# current-meter.net
KiCad netlist of a schematic drawn in Altium Designer
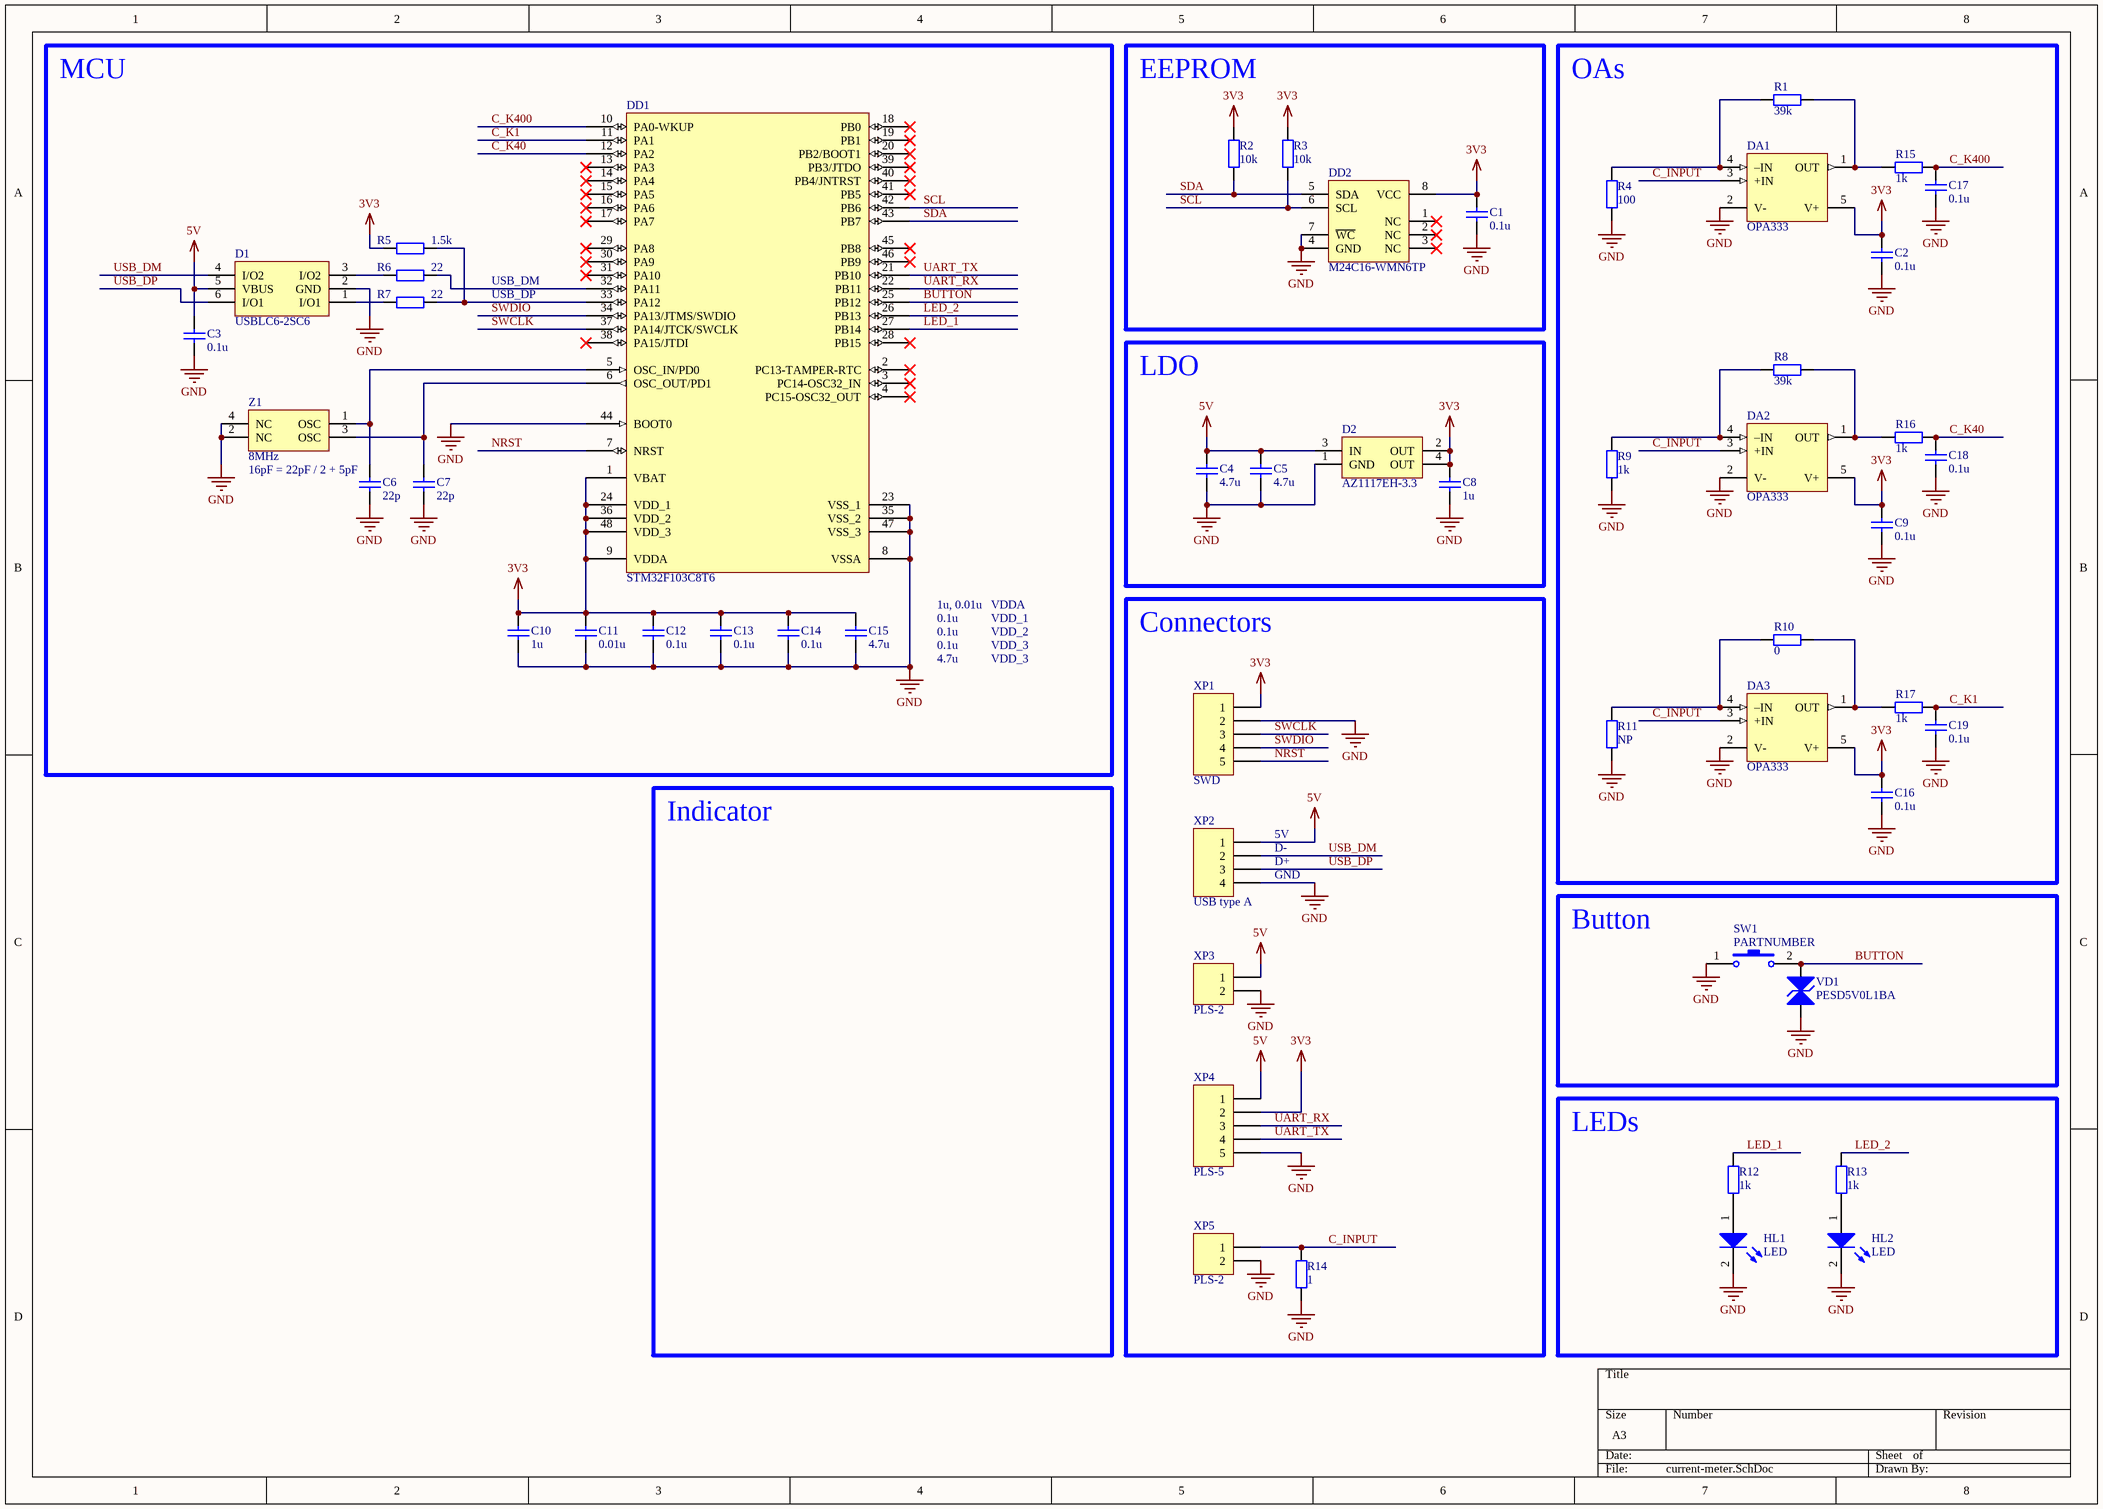
[diagram p0: current-meter.SchDoc]

(export (version "E")
  (design (tool "Eeschema 10.0.6"))
  (components
    (comp (ref "C1")
      (value "0.1u")
      (footprint "0603-CAP")
      (description "PARTNUMBER")
      (libsource (lib "Miscellaneous Devices") (part "Cap"))
    )
    (comp (ref "C2")
      (value "0.1u")
      (footprint "0603-CAP")
      (description "PARTNUMBER")
      (libsource (lib "Miscellaneous Devices") (part "Cap"))
    )
    (comp (ref "C3")
      (value "0.1u")
      (footprint "0603-CAP")
      (description "PARTNUMBER")
      (libsource (lib "Miscellaneous Devices") (part "Cap"))
    )
    (comp (ref "C4")
      (value "4.7u")
      (footprint "0805-CAP")
      (description "PARTNUMBER")
      (libsource (lib "Miscellaneous Devices") (part "Cap"))
    )
    (comp (ref "C5")
      (value "4.7u")
      (footprint "0805-CAP")
      (description "PARTNUMBER")
      (libsource (lib "Miscellaneous Devices") (part "Cap"))
    )
    (comp (ref "C6")
      (value "22p")
      (footprint "0603-CAP")
      (description "PARTNUMBER")
      (libsource (lib "Miscellaneous Devices") (part "Cap"))
    )
    (comp (ref "C7")
      (value "22p")
      (footprint "0603-CAP")
      (description "PARTNUMBER")
      (libsource (lib "Miscellaneous Devices") (part "Cap"))
    )
    (comp (ref "C8")
      (value "1u")
      (footprint "0805-CAP")
      (description "PARTNUMBER")
      (libsource (lib "Miscellaneous Devices") (part "Cap"))
    )
    (comp (ref "C9")
      (value "0.1u")
      (footprint "0603-CAP")
      (description "PARTNUMBER")
      (libsource (lib "Miscellaneous Devices") (part "Cap"))
    )
    (comp (ref "C10")
      (value "1u")
      (footprint "0805-CAP")
      (description "PARTNUMBER")
      (libsource (lib "Miscellaneous Devices") (part "Cap"))
    )
    (comp (ref "C11")
      (value "0.01u")
      (footprint "0603-CAP")
      (description "PARTNUMBER")
      (libsource (lib "Miscellaneous Devices") (part "Cap"))
    )
    (comp (ref "C12")
      (value "0.1u")
      (footprint "0603-CAP")
      (description "PARTNUMBER")
      (libsource (lib "Miscellaneous Devices") (part "Cap"))
    )
    (comp (ref "C13")
      (value "0.1u")
      (footprint "0603-CAP")
      (description "PARTNUMBER")
      (libsource (lib "Miscellaneous Devices") (part "Cap"))
    )
    (comp (ref "C14")
      (value "0.1u")
      (footprint "0603-CAP")
      (description "PARTNUMBER")
      (libsource (lib "Miscellaneous Devices") (part "Cap"))
    )
    (comp (ref "C15")
      (value "4.7u")
      (footprint "0805-CAP")
      (description "PARTNUMBER")
      (libsource (lib "Miscellaneous Devices") (part "Cap"))
    )
    (comp (ref "C16")
      (value "0.1u")
      (footprint "0603-CAP")
      (description "PARTNUMBER")
      (libsource (lib "Miscellaneous Devices") (part "Cap"))
    )
    (comp (ref "C17")
      (value "0.1u")
      (footprint "0603-CAP")
      (description "PARTNUMBER")
      (libsource (lib "Miscellaneous Devices") (part "Cap"))
    )
    (comp (ref "C18")
      (value "0.1u")
      (footprint "0603-CAP")
      (description "PARTNUMBER")
      (libsource (lib "Miscellaneous Devices") (part "Cap"))
    )
    (comp (ref "C19")
      (value "0.1u")
      (footprint "0603-CAP")
      (description "PARTNUMBER")
      (libsource (lib "Miscellaneous Devices") (part "Cap"))
    )
    (comp (ref "D1")
      (value "USBLC6-2SC6")
      (footprint "SOT-23-6L")
      (libsource (lib "sp-sharer-pcb") (part "USBLC6-2SC6"))
    )
    (comp (ref "D2")
      (value "AZ1117EH-3.3")
      (footprint "SOT-223")
      (description "AZ1117EH-3.3TRG1")
      (libsource (lib "sp-sharer-pcb") (part "AZ1117EH-3.3"))
    )
    (comp (ref "DA1")
      (value "OPA333")
      (footprint "SOT-23-5")
      (description "OPA333AIDBVR (TS321ILT)")
      (libsource (lib "current-meter") (part "OPA333"))
    )
    (comp (ref "DA2")
      (value "OPA333")
      (footprint "SOT-23-5")
      (description "OPA333AIDBVR (TS321ILT)")
      (libsource (lib "current-meter") (part "OPA333"))
    )
    (comp (ref "DA3")
      (value "OPA333")
      (footprint "SOT-23-5")
      (description "OPA333AIDBVR (TS321ILT)")
      (libsource (lib "current-meter") (part "OPA333"))
    )
    (comp (ref "DD1")
      (value "STM32F103C8T6")
      (footprint "LQFP48")
      (libsource (lib "sp-sharer-pcb") (part "STM32F103C8T6"))
    )
    (comp (ref "DD2")
      (value "M24C16-WMN6TP")
      (footprint "SOIC8")
      (libsource (lib "sp-sharer-pcb") (part "M24C16-WMN6TP"))
    )
    (comp (ref "HL1")
      (value "LED")
      (footprint "0603-LED")
      (description "PARTNUMBER")
      (libsource (lib "Miscellaneous Devices") (part "LED0"))
    )
    (comp (ref "HL2")
      (value "LED")
      (footprint "0603-LED")
      (description "PARTNUMBER")
      (libsource (lib "Miscellaneous Devices") (part "LED0"))
    )
    (comp (ref "R1")
      (value "39k")
      (footprint "0603-RES")
      (description "PARTNUMBER")
      (libsource (lib "") (part "Res2_3"))
    )
    (comp (ref "R2")
      (value "10k")
      (footprint "0603-RES")
      (description "PARTNUMBER")
      (libsource (lib "") (part "Res2_1"))
    )
    (comp (ref "R3")
      (value "10k")
      (footprint "0603-RES")
      (description "PARTNUMBER")
      (libsource (lib "") (part "Res2_1"))
    )
    (comp (ref "R4")
      (value "100")
      (footprint "0603-RES")
      (description "PARTNUMBER")
      (libsource (lib "Miscellaneous Devices") (part "Res2"))
    )
    (comp (ref "R5")
      (value "1.5k")
      (footprint "0603-RES")
      (description "PARTNUMBER")
      (libsource (lib "") (part "Res2_2"))
    )
    (comp (ref "R6")
      (value "22")
      (footprint "0603-RES")
      (description "PARTNUMBER")
      (libsource (lib "") (part "Res2_2"))
    )
    (comp (ref "R7")
      (value "22")
      (footprint "0603-RES")
      (description "PARTNUMBER")
      (libsource (lib "") (part "Res2_2"))
    )
    (comp (ref "R8")
      (value "39k")
      (footprint "0603-RES")
      (description "PARTNUMBER")
      (libsource (lib "") (part "Res2_3"))
    )
    (comp (ref "R9")
      (value "1k")
      (footprint "0603-RES")
      (description "PARTNUMBER")
      (libsource (lib "Miscellaneous Devices") (part "Res2"))
    )
    (comp (ref "R10")
      (value "0")
      (footprint "0603-RES")
      (description "PARTNUMBER")
      (libsource (lib "") (part "Res2_3"))
    )
    (comp (ref "R11")
      (value "NP")
      (footprint "0603-RES")
      (description "PARTNUMBER")
      (libsource (lib "Miscellaneous Devices") (part "Res2"))
    )
    (comp (ref "R12")
      (value "1k")
      (footprint "0603-RES")
      (description "PARTNUMBER")
      (libsource (lib "Miscellaneous Devices") (part "Res2"))
    )
    (comp (ref "R13")
      (value "1k")
      (footprint "0603-RES")
      (description "PARTNUMBER")
      (libsource (lib "Miscellaneous Devices") (part "Res2"))
    )
    (comp (ref "R14")
      (value "1")
      (footprint "1206-RES")
      (description "PARTNUMBER")
      (libsource (lib "Miscellaneous Devices") (part "Res2"))
    )
    (comp (ref "R15")
      (value "1k")
      (footprint "0603-RES")
      (description "PARTNUMBER")
      (libsource (lib "") (part "Res2_2"))
    )
    (comp (ref "R16")
      (value "1k")
      (footprint "0603-RES")
      (description "PARTNUMBER")
      (libsource (lib "") (part "Res2_2"))
    )
    (comp (ref "R17")
      (value "1k")
      (footprint "0603-RES")
      (description "PARTNUMBER")
      (libsource (lib "") (part "Res2_2"))
    )
    (comp (ref "SW1")
      (value "PARTNUMBER")
      (footprint "KLS7-TS3608-5.0-180")
      (libsource (lib "Miscellaneous Devices") (part "SW-PB"))
    )
    (comp (ref "VD1")
      (value "PESD5V0L1BA")
      (footprint "SOD-323")
      (description "PESD5V0L1BA,115")
      (libsource (lib "radio-device") (part "TVS diode"))
    )
    (comp (ref "XP1")
      (value "SWD")
      (footprint "PLS-5")
      (description "PARTNUMBER")
      (libsource (lib "Miscellaneous Connectors") (part "Header 5"))
    )
    (comp (ref "XP2")
      (value "USB type A")
      (footprint "DS1098-B")
      (description "PARTNUMBER")
      (libsource (lib "Miscellaneous Connectors") (part "Header 4"))
    )
    (comp (ref "XP3")
      (value "NO POP")
      (footprint "PLS-2")
      (description "PLS-2")
      (fields (field (name "TYPE") "PLS-2"))
      (libsource (lib "Miscellaneous Connectors") (part "Header 2"))
    )
    (comp (ref "XP4")
      (value "PLS-5")
      (footprint "PLS-5")
      (description "PARTNUMBER")
      (libsource (lib "Miscellaneous Connectors") (part "Header 5"))
    )
    (comp (ref "XP5")
      (value "NO POP")
      (footprint "PLS-2")
      (description "PLS-2")
      (fields (field (name "TYPE") "PLS-2"))
      (libsource (lib "Miscellaneous Connectors") (part "Header 2"))
    )
    (comp (ref "Z1")
      (value "8MHz")
      (footprint "KX-9")
      (description "12.89048 (12.89007 -20+70)")
      (libsource (lib "sp-sharer-pcb") (part "KX-9AT"))
    )
  )
  (nets
    (net (code "1") (name "/BUTTON") (class "Default")
      (node (ref "DD1") (pin "25") (pinfunction "PB12_25") (pintype "bidirectional"))
      (node (ref "SW1") (pin "2") (pinfunction "2_2") (pintype "passive"))
      (node (ref "VD1") (pin "1") (pinfunction "A_1") (pintype "passive"))
    )
    (net (code "2") (name "/C_INPUT") (class "Default")
      (node (ref "DA1") (pin "3") (pinfunction "+IN_3") (pintype "input"))
      (node (ref "DA2") (pin "3") (pinfunction "+IN_3") (pintype "input"))
      (node (ref "DA3") (pin "3") (pinfunction "+IN_3") (pintype "input"))
      (node (ref "R14") (pin "2") (pinfunction "2_2") (pintype "passive"))
      (node (ref "XP5") (pin "1") (pinfunction "1_1") (pintype "passive"))
    )
    (net (code "3") (name "/C_K1") (class "Default")
      (node (ref "C19") (pin "1") (pinfunction "1_1") (pintype "passive"))
      (node (ref "DD1") (pin "11") (pinfunction "PA1_11") (pintype "bidirectional"))
      (node (ref "R17") (pin "1") (pinfunction "1_1") (pintype "passive"))
    )
    (net (code "4") (name "/C_K40") (class "Default")
      (node (ref "C18") (pin "1") (pinfunction "1_1") (pintype "passive"))
      (node (ref "DD1") (pin "12") (pinfunction "PA2_12") (pintype "bidirectional"))
      (node (ref "R16") (pin "1") (pinfunction "1_1") (pintype "passive"))
    )
    (net (code "5") (name "/C_K400") (class "Default")
      (node (ref "C17") (pin "1") (pinfunction "1_1") (pintype "passive"))
      (node (ref "DD1") (pin "10") (pinfunction "PA0-WKUP_10") (pintype "bidirectional"))
      (node (ref "R15") (pin "1") (pinfunction "1_1") (pintype "passive"))
    )
    (net (code "6") (name "/LED_1") (class "Default")
      (node (ref "DD1") (pin "27") (pinfunction "PB14_27") (pintype "bidirectional"))
      (node (ref "R12") (pin "2") (pinfunction "2_2") (pintype "passive"))
    )
    (net (code "7") (name "/LED_2") (class "Default")
      (node (ref "DD1") (pin "26") (pinfunction "PB13_26") (pintype "bidirectional"))
      (node (ref "R13") (pin "2") (pinfunction "2_2") (pintype "passive"))
    )
    (net (code "8") (name "/NRST") (class "Default")
      (node (ref "DD1") (pin "7") (pinfunction "NRST_7") (pintype "bidirectional"))
      (node (ref "XP1") (pin "5") (pinfunction "5_5") (pintype "passive"))
    )
    (net (code "9") (name "/SCL") (class "Default")
      (node (ref "DD1") (pin "42") (pinfunction "PB6_42") (pintype "bidirectional"))
      (node (ref "DD2") (pin "6") (pinfunction "SCL_6") (pintype "passive"))
      (node (ref "R3") (pin "2") (pinfunction "2_2") (pintype "passive"))
    )
    (net (code "10") (name "/SDA") (class "Default")
      (node (ref "DD1") (pin "43") (pinfunction "PB7_43") (pintype "bidirectional"))
      (node (ref "DD2") (pin "5") (pinfunction "SDA_5") (pintype "passive"))
      (node (ref "R2") (pin "2") (pinfunction "2_2") (pintype "passive"))
    )
    (net (code "11") (name "/SWCLK") (class "Default")
      (node (ref "DD1") (pin "37") (pinfunction "PA14/JTCK/SWCLK_37") (pintype "bidirectional"))
      (node (ref "XP1") (pin "3") (pinfunction "3_3") (pintype "passive"))
    )
    (net (code "12") (name "/SWDIO") (class "Default")
      (node (ref "DD1") (pin "34") (pinfunction "PA13/JTMS/SWDIO_34") (pintype "bidirectional"))
      (node (ref "XP1") (pin "4") (pinfunction "4_4") (pintype "passive"))
    )
    (net (code "13") (name "/UART_RX") (class "Default")
      (node (ref "DD1") (pin "22") (pinfunction "PB11_22") (pintype "bidirectional"))
      (node (ref "XP4") (pin "3") (pinfunction "3_3") (pintype "passive"))
    )
    (net (code "14") (name "/UART_TX") (class "Default")
      (node (ref "DD1") (pin "21") (pinfunction "PB10_21") (pintype "bidirectional"))
      (node (ref "XP4") (pin "4") (pinfunction "4_4") (pintype "passive"))
    )
    (net (code "15") (name "/USB_DM") (class "Default")
      (node (ref "D1") (pin "4") (pinfunction "I/O2_4") (pintype "passive"))
      (node (ref "XP2") (pin "2") (pinfunction "2_2") (pintype "passive"))
    )
    (net (code "16") (name "/USB_DP") (class "Default")
      (node (ref "D1") (pin "6") (pinfunction "I/O1_6") (pintype "passive"))
      (node (ref "XP2") (pin "3") (pinfunction "3_3") (pintype "passive"))
    )
    (net (code "17") (name "3V3") (class "Default")
      (node (ref "C1") (pin "1") (pinfunction "1_1") (pintype "passive"))
      (node (ref "C10") (pin "2") (pinfunction "2_2") (pintype "passive"))
      (node (ref "C11") (pin "2") (pinfunction "2_2") (pintype "passive"))
      (node (ref "C12") (pin "2") (pinfunction "2_2") (pintype "passive"))
      (node (ref "C13") (pin "2") (pinfunction "2_2") (pintype "passive"))
      (node (ref "C14") (pin "2") (pinfunction "2_2") (pintype "passive"))
      (node (ref "C15") (pin "2") (pinfunction "2_2") (pintype "passive"))
      (node (ref "C16") (pin "2") (pinfunction "2_2") (pintype "passive"))
      (node (ref "C2") (pin "2") (pinfunction "2_2") (pintype "passive"))
      (node (ref "C8") (pin "1") (pinfunction "1_1") (pintype "passive"))
      (node (ref "C9") (pin "2") (pinfunction "2_2") (pintype "passive"))
      (node (ref "D2") (pin "2") (pinfunction "OUT_2") (pintype "power_in"))
      (node (ref "D2") (pin "4") (pinfunction "OUT_4") (pintype "power_in"))
      (node (ref "DA1") (pin "5") (pinfunction "V+_5") (pintype "passive"))
      (node (ref "DA2") (pin "5") (pinfunction "V+_5") (pintype "passive"))
      (node (ref "DA3") (pin "5") (pinfunction "V+_5") (pintype "passive"))
      (node (ref "DD1") (pin "1") (pinfunction "VBAT_1") (pintype "power_in"))
      (node (ref "DD1") (pin "24") (pinfunction "VDD_1_24") (pintype "power_in"))
      (node (ref "DD1") (pin "36") (pinfunction "VDD_2_36") (pintype "power_in"))
      (node (ref "DD1") (pin "48") (pinfunction "VDD_3_48") (pintype "power_in"))
      (node (ref "DD1") (pin "9") (pinfunction "VDDA_9") (pintype "power_in"))
      (node (ref "DD2") (pin "8") (pinfunction "VCC_8") (pintype "passive"))
      (node (ref "R2") (pin "1") (pinfunction "1_1") (pintype "passive"))
      (node (ref "R3") (pin "1") (pinfunction "1_1") (pintype "passive"))
      (node (ref "R5") (pin "2") (pinfunction "2_2") (pintype "passive"))
      (node (ref "XP1") (pin "1") (pinfunction "1_1") (pintype "passive"))
      (node (ref "XP4") (pin "2") (pinfunction "2_2") (pintype "passive"))
    )
    (net (code "18") (name "5V") (class "Default")
      (node (ref "C3") (pin "1") (pinfunction "1_1") (pintype "passive"))
      (node (ref "C4") (pin "1") (pinfunction "1_1") (pintype "passive"))
      (node (ref "C5") (pin "1") (pinfunction "1_1") (pintype "passive"))
      (node (ref "D1") (pin "5") (pinfunction "VBUS_5") (pintype "passive"))
      (node (ref "D2") (pin "3") (pinfunction "IN_3") (pintype "power_in"))
      (node (ref "XP2") (pin "1") (pinfunction "1_1") (pintype "passive"))
      (node (ref "XP3") (pin "1") (pinfunction "1_1") (pintype "passive"))
      (node (ref "XP4") (pin "1") (pinfunction "1_1") (pintype "passive"))
    )
    (net (code "19") (name "GND") (class "Default")
      (node (ref "C1") (pin "2") (pinfunction "2_2") (pintype "passive"))
      (node (ref "C10") (pin "1") (pinfunction "1_1") (pintype "passive"))
      (node (ref "C11") (pin "1") (pinfunction "1_1") (pintype "passive"))
      (node (ref "C12") (pin "1") (pinfunction "1_1") (pintype "passive"))
      (node (ref "C13") (pin "1") (pinfunction "1_1") (pintype "passive"))
      (node (ref "C14") (pin "1") (pinfunction "1_1") (pintype "passive"))
      (node (ref "C15") (pin "1") (pinfunction "1_1") (pintype "passive"))
      (node (ref "C16") (pin "1") (pinfunction "1_1") (pintype "passive"))
      (node (ref "C17") (pin "2") (pinfunction "2_2") (pintype "passive"))
      (node (ref "C18") (pin "2") (pinfunction "2_2") (pintype "passive"))
      (node (ref "C19") (pin "2") (pinfunction "2_2") (pintype "passive"))
      (node (ref "C2") (pin "1") (pinfunction "1_1") (pintype "passive"))
      (node (ref "C3") (pin "2") (pinfunction "2_2") (pintype "passive"))
      (node (ref "C4") (pin "2") (pinfunction "2_2") (pintype "passive"))
      (node (ref "C5") (pin "2") (pinfunction "2_2") (pintype "passive"))
      (node (ref "C6") (pin "2") (pinfunction "2_2") (pintype "passive"))
      (node (ref "C7") (pin "2") (pinfunction "2_2") (pintype "passive"))
      (node (ref "C8") (pin "2") (pinfunction "2_2") (pintype "passive"))
      (node (ref "C9") (pin "1") (pinfunction "1_1") (pintype "passive"))
      (node (ref "D1") (pin "2") (pinfunction "GND_2") (pintype "passive"))
      (node (ref "D2") (pin "1") (pinfunction "GND_1") (pintype "power_in"))
      (node (ref "DA1") (pin "2") (pinfunction "V-_2") (pintype "passive"))
      (node (ref "DA2") (pin "2") (pinfunction "V-_2") (pintype "passive"))
      (node (ref "DA3") (pin "2") (pinfunction "V-_2") (pintype "passive"))
      (node (ref "DD1") (pin "23") (pinfunction "VSS_1_23") (pintype "power_in"))
      (node (ref "DD1") (pin "35") (pinfunction "VSS_2_35") (pintype "power_in"))
      (node (ref "DD1") (pin "44") (pinfunction "BOOT0_44") (pintype "input"))
      (node (ref "DD1") (pin "47") (pinfunction "VSS_3_47") (pintype "power_in"))
      (node (ref "DD1") (pin "8") (pinfunction "VSSA_8") (pintype "power_in"))
      (node (ref "DD2") (pin "4") (pinfunction "GND_4") (pintype "passive"))
      (node (ref "DD2") (pin "7") (pinfunction "~{WC}_7") (pintype "passive"))
      (node (ref "HL1") (pin "2") (pinfunction "K_2") (pintype "passive"))
      (node (ref "HL2") (pin "2") (pinfunction "K_2") (pintype "passive"))
      (node (ref "R11") (pin "1") (pinfunction "1_1") (pintype "passive"))
      (node (ref "R14") (pin "1") (pinfunction "1_1") (pintype "passive"))
      (node (ref "R4") (pin "1") (pinfunction "1_1") (pintype "passive"))
      (node (ref "R9") (pin "1") (pinfunction "1_1") (pintype "passive"))
      (node (ref "SW1") (pin "1") (pinfunction "1_1") (pintype "passive"))
      (node (ref "VD1") (pin "2") (pinfunction "K_2") (pintype "passive"))
      (node (ref "XP1") (pin "2") (pinfunction "2_2") (pintype "passive"))
      (node (ref "XP2") (pin "4") (pinfunction "4_4") (pintype "passive"))
      (node (ref "XP3") (pin "2") (pinfunction "2_2") (pintype "passive"))
      (node (ref "XP4") (pin "5") (pinfunction "5_5") (pintype "passive"))
      (node (ref "XP5") (pin "2") (pinfunction "2_2") (pintype "passive"))
      (node (ref "Z1") (pin "2") (pinfunction "NC_2") (pintype "passive"))
      (node (ref "Z1") (pin "4") (pinfunction "NC_4") (pintype "passive"))
    )
    (net (code "20") (name "Net-(D1-I{slash}O1-Pad1)") (class "Default")
      (node (ref "D1") (pin "1") (pinfunction "I/O1_1") (pintype "passive"))
      (node (ref "R7") (pin "2") (pinfunction "2_2") (pintype "passive"))
    )
    (net (code "21") (name "Net-(D1-I{slash}O2-Pad3)") (class "Default")
      (node (ref "D1") (pin "3") (pinfunction "I/O2_3") (pintype "passive"))
      (node (ref "R6") (pin "2") (pinfunction "2_2") (pintype "passive"))
    )
    (net (code "22") (name "Net-(DA1-OUT)") (class "Default")
      (node (ref "DA1") (pin "1") (pinfunction "OUT_1") (pintype "output"))
      (node (ref "R1") (pin "2") (pinfunction "2_2") (pintype "passive"))
      (node (ref "R15") (pin "2") (pinfunction "2_2") (pintype "passive"))
    )
    (net (code "23") (name "Net-(DA1-–IN)") (class "Default")
      (node (ref "DA1") (pin "4") (pinfunction "–IN_4") (pintype "input"))
      (node (ref "R1") (pin "1") (pinfunction "1_1") (pintype "passive"))
      (node (ref "R4") (pin "2") (pinfunction "2_2") (pintype "passive"))
    )
    (net (code "24") (name "Net-(DA2-OUT)") (class "Default")
      (node (ref "DA2") (pin "1") (pinfunction "OUT_1") (pintype "output"))
      (node (ref "R16") (pin "2") (pinfunction "2_2") (pintype "passive"))
      (node (ref "R8") (pin "2") (pinfunction "2_2") (pintype "passive"))
    )
    (net (code "25") (name "Net-(DA2-–IN)") (class "Default")
      (node (ref "DA2") (pin "4") (pinfunction "–IN_4") (pintype "input"))
      (node (ref "R8") (pin "1") (pinfunction "1_1") (pintype "passive"))
      (node (ref "R9") (pin "2") (pinfunction "2_2") (pintype "passive"))
    )
    (net (code "26") (name "Net-(DA3-OUT)") (class "Default")
      (node (ref "DA3") (pin "1") (pinfunction "OUT_1") (pintype "output"))
      (node (ref "R10") (pin "2") (pinfunction "2_2") (pintype "passive"))
      (node (ref "R17") (pin "2") (pinfunction "2_2") (pintype "passive"))
    )
    (net (code "27") (name "Net-(DA3-–IN)") (class "Default")
      (node (ref "DA3") (pin "4") (pinfunction "–IN_4") (pintype "input"))
      (node (ref "R10") (pin "1") (pinfunction "1_1") (pintype "passive"))
      (node (ref "R11") (pin "2") (pinfunction "2_2") (pintype "passive"))
    )
    (net (code "28") (name "Net-(DD1-OSC_IN{slash}PD0)") (class "Default")
      (node (ref "C6") (pin "1") (pinfunction "1_1") (pintype "passive"))
      (node (ref "DD1") (pin "5") (pinfunction "OSC_IN/PD0_5") (pintype "input"))
      (node (ref "Z1") (pin "1") (pinfunction "OSC_1") (pintype "passive"))
    )
    (net (code "29") (name "Net-(DD1-OSC_OUT{slash}PD1)") (class "Default")
      (node (ref "C7") (pin "1") (pinfunction "1_1") (pintype "passive"))
      (node (ref "DD1") (pin "6") (pinfunction "OSC_OUT/PD1_6") (pintype "output"))
      (node (ref "Z1") (pin "3") (pinfunction "OSC_3") (pintype "passive"))
    )
    (net (code "30") (name "Net-(DD1-PA11)") (class "Default")
      (node (ref "DD1") (pin "32") (pinfunction "PA11_32") (pintype "bidirectional"))
      (node (ref "R6") (pin "1") (pinfunction "1_1") (pintype "passive"))
    )
    (net (code "31") (name "Net-(DD1-PA12)") (class "Default")
      (node (ref "DD1") (pin "33") (pinfunction "PA12_33") (pintype "bidirectional"))
      (node (ref "R5") (pin "1") (pinfunction "1_1") (pintype "passive"))
      (node (ref "R7") (pin "1") (pinfunction "1_1") (pintype "passive"))
    )
    (net (code "32") (name "Net-(HL1-A)") (class "Default")
      (node (ref "HL1") (pin "1") (pinfunction "A_1") (pintype "passive"))
      (node (ref "R12") (pin "1") (pinfunction "1_1") (pintype "passive"))
    )
    (net (code "33") (name "Net-(HL2-A)") (class "Default")
      (node (ref "HL2") (pin "1") (pinfunction "A_1") (pintype "passive"))
      (node (ref "R13") (pin "1") (pinfunction "1_1") (pintype "passive"))
    )
    (net (code "34") (name "unconnected-(DD1-PA3-Pad13)") (class "Default")
      (node (ref "DD1") (pin "13") (pinfunction "PA3_13") (pintype "bidirectional+no_connect"))
    )
    (net (code "35") (name "unconnected-(DD1-PA4-Pad14)") (class "Default")
      (node (ref "DD1") (pin "14") (pinfunction "PA4_14") (pintype "bidirectional+no_connect"))
    )
    (net (code "36") (name "unconnected-(DD1-PA5-Pad15)") (class "Default")
      (node (ref "DD1") (pin "15") (pinfunction "PA5_15") (pintype "bidirectional+no_connect"))
    )
    (net (code "37") (name "unconnected-(DD1-PA6-Pad16)") (class "Default")
      (node (ref "DD1") (pin "16") (pinfunction "PA6_16") (pintype "bidirectional+no_connect"))
    )
    (net (code "38") (name "unconnected-(DD1-PA7-Pad17)") (class "Default")
      (node (ref "DD1") (pin "17") (pinfunction "PA7_17") (pintype "bidirectional+no_connect"))
    )
    (net (code "39") (name "unconnected-(DD1-PA8-Pad29)") (class "Default")
      (node (ref "DD1") (pin "29") (pinfunction "PA8_29") (pintype "bidirectional+no_connect"))
    )
    (net (code "40") (name "unconnected-(DD1-PA9-Pad30)") (class "Default")
      (node (ref "DD1") (pin "30") (pinfunction "PA9_30") (pintype "bidirectional+no_connect"))
    )
    (net (code "41") (name "unconnected-(DD1-PA10-Pad31)") (class "Default")
      (node (ref "DD1") (pin "31") (pinfunction "PA10_31") (pintype "bidirectional+no_connect"))
    )
    (net (code "42") (name "unconnected-(DD1-PA15{slash}JTDI-Pad38)") (class "Default")
      (node (ref "DD1") (pin "38") (pinfunction "PA15/JTDI_38") (pintype "bidirectional+no_connect"))
    )
    (net (code "43") (name "unconnected-(DD1-PB0-Pad18)") (class "Default")
      (node (ref "DD1") (pin "18") (pinfunction "PB0_18") (pintype "bidirectional+no_connect"))
    )
    (net (code "44") (name "unconnected-(DD1-PB1-Pad19)") (class "Default")
      (node (ref "DD1") (pin "19") (pinfunction "PB1_19") (pintype "bidirectional+no_connect"))
    )
    (net (code "45") (name "unconnected-(DD1-PB2{slash}BOOT1-Pad20)") (class "Default")
      (node (ref "DD1") (pin "20") (pinfunction "PB2/BOOT1_20") (pintype "bidirectional+no_connect"))
    )
    (net (code "46") (name "unconnected-(DD1-PB3{slash}JTDO-Pad39)") (class "Default")
      (node (ref "DD1") (pin "39") (pinfunction "PB3/JTDO_39") (pintype "bidirectional+no_connect"))
    )
    (net (code "47") (name "unconnected-(DD1-PB4{slash}JNTRST-Pad40)") (class "Default")
      (node (ref "DD1") (pin "40") (pinfunction "PB4/JNTRST_40") (pintype "bidirectional+no_connect"))
    )
    (net (code "48") (name "unconnected-(DD1-PB5-Pad41)") (class "Default")
      (node (ref "DD1") (pin "41") (pinfunction "PB5_41") (pintype "bidirectional+no_connect"))
    )
    (net (code "49") (name "unconnected-(DD1-PB8-Pad45)") (class "Default")
      (node (ref "DD1") (pin "45") (pinfunction "PB8_45") (pintype "bidirectional+no_connect"))
    )
    (net (code "50") (name "unconnected-(DD1-PB9-Pad46)") (class "Default")
      (node (ref "DD1") (pin "46") (pinfunction "PB9_46") (pintype "bidirectional+no_connect"))
    )
    (net (code "51") (name "unconnected-(DD1-PB15-Pad28)") (class "Default")
      (node (ref "DD1") (pin "28") (pinfunction "PB15_28") (pintype "bidirectional+no_connect"))
    )
    (net (code "52") (name "unconnected-(DD1-PC13-TAMPER-RTC-Pad2)") (class "Default")
      (node (ref "DD1") (pin "2") (pinfunction "PC13-TAMPER-RTC_2") (pintype "bidirectional+no_connect"))
    )
    (net (code "53") (name "unconnected-(DD1-PC14-OSC32_IN-Pad3)") (class "Default")
      (node (ref "DD1") (pin "3") (pinfunction "PC14-OSC32_IN_3") (pintype "bidirectional+no_connect"))
    )
    (net (code "54") (name "unconnected-(DD1-PC15-OSC32_OUT-Pad4)") (class "Default")
      (node (ref "DD1") (pin "4") (pinfunction "PC15-OSC32_OUT_4") (pintype "bidirectional+no_connect"))
    )
    (net (code "55") (name "unconnected-(DD2-NC-Pad1)") (class "Default")
      (node (ref "DD2") (pin "1") (pinfunction "NC_1") (pintype "passive+no_connect"))
    )
    (net (code "56") (name "unconnected-(DD2-NC-Pad2)") (class "Default")
      (node (ref "DD2") (pin "2") (pinfunction "NC_2") (pintype "passive+no_connect"))
    )
    (net (code "57") (name "unconnected-(DD2-NC-Pad3)") (class "Default")
      (node (ref "DD2") (pin "3") (pinfunction "NC_3") (pintype "passive+no_connect"))
    )
  )
)
